# 05_MCU_PC.net
KiCad netlist of a schematic drawn in Altium Designer
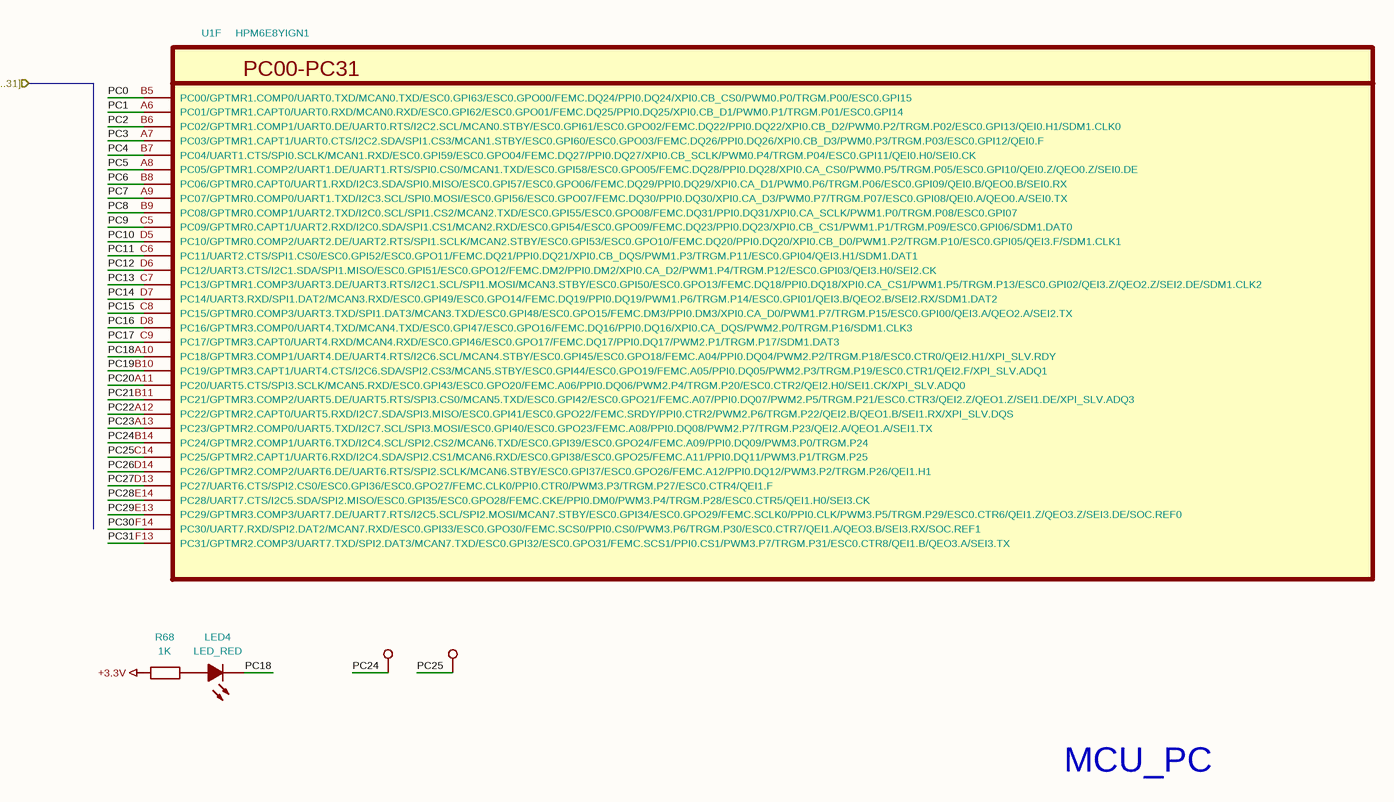
[diagram p0: 05.MCU_PC.SchDoc]

(export (version "E")
  (design (tool "Eeschema 10.0.6"))
  (components
    (comp (ref "LED4") (value "LED_RED") (libsource (lib "01-HPM-Peripheral") (part "LED_RED")))
    (comp (ref "R68") (value "1K") (libsource (lib "02_HPM_Resistor") (part "1K_0402")))
    (comp (ref "TP33") (value "0.5mm") (libsource (lib "01-HPM-Peripheral") (part "TestPoint-0.5mm")))
    (comp (ref "TP35") (value "0.5mm") (libsource (lib "01-HPM-Peripheral") (part "TestPoint-0.5mm")))
    (comp (ref "U1") (value "HPM6E8YIGN1") (libsource (lib "HPM6E00") (part "HPM6E8YIGN1")))
  )
  (nets
    (net (code "1") (name "+3.3V") (class "Default")
      (node (ref "R68") (pin "1") (pinfunction "1_1") (pintype "passive"))
    )
    (net (code "2") (name "/PC0") (class "Default")
      (node (ref "U1") (pin "B5") (pinfunction "PC00/GPTMR1.COMP0/UART0.TXD/MCAN0.TXD/ESC0.GPI63/ESC0.GPO00/FEMC.DQ24/PPI0.DQ24/XPI0.CB_CS0/PWM0.P0/TRGM.P00/ESC0.GPI15_B5") (pintype "passive"))
    )
    (net (code "3") (name "/PC1") (class "Default")
      (node (ref "U1") (pin "A6") (pinfunction "PC01/GPTMR1.CAPT0/UART0.RXD/MCAN0.RXD/ESC0.GPI62/ESC0.GPO01/FEMC.DQ25/PPI0.DQ25/XPI0.CB_D1/PWM0.P1/TRGM.P01/ESC0.GPI14_A6") (pintype "passive"))
    )
    (net (code "4") (name "/PC2") (class "Default")
      (node (ref "U1") (pin "B6") (pinfunction "PC02/GPTMR1.COMP1/UART0.DE/UART0.RTS/I2C2.SCL/MCAN0.STBY/ESC0.GPI61/ESC0.GPO02/FEMC.DQ22/PPI0.DQ22/XPI0.CB_D2/PWM0.P2/TRGM.P02/ESC0.GPI13/QEI0.H1/SDM1.CLK0_B6") (pintype "passive"))
    )
    (net (code "5") (name "/PC3") (class "Default")
      (node (ref "U1") (pin "A7") (pinfunction "PC03/GPTMR1.CAPT1/UART0.CTS/I2C2.SDA/SPI1.CS3/MCAN1.STBY/ESC0.GPI60/ESC0.GPO03/FEMC.DQ26/PPI0.DQ26/XPI0.CB_D3/PWM0.P3/TRGM.P03/ESC0.GPI12/QEI0.F_A7") (pintype "passive"))
    )
    (net (code "6") (name "/PC4") (class "Default")
      (node (ref "U1") (pin "B7") (pinfunction "PC04/UART1.CTS/SPI0.SCLK/MCAN1.RXD/ESC0.GPI59/ESC0.GPO04/FEMC.DQ27/PPI0.DQ27/XPI0.CB_SCLK/PWM0.P4/TRGM.P04/ESC0.GPI11/QEI0.H0/SEI0.CK_B7") (pintype "passive"))
    )
    (net (code "7") (name "/PC5") (class "Default")
      (node (ref "U1") (pin "A8") (pinfunction "PC05/GPTMR1.COMP2/UART1.DE/UART1.RTS/SPI0.CS0/MCAN1.TXD/ESC0.GPI58/ESC0.GPO05/FEMC.DQ28/PPI0.DQ28/XPI0.CA_CS0/PWM0.P5/TRGM.P05/ESC0.GPI10/QEI0.Z/QEO0.Z/SEI0.DE_A8") (pintype "passive"))
    )
    (net (code "8") (name "/PC6") (class "Default")
      (node (ref "U1") (pin "B8") (pinfunction "PC06/GPTMR0.CAPT0/UART1.RXD/I2C3.SDA/SPI0.MISO/ESC0.GPI57/ESC0.GPO06/FEMC.DQ29/PPI0.DQ29/XPI0.CA_D1/PWM0.P6/TRGM.P06/ESC0.GPI09/QEI0.B/QEO0.B/SEI0.RX_B8") (pintype "passive"))
    )
    (net (code "9") (name "/PC7") (class "Default")
      (node (ref "U1") (pin "A9") (pinfunction "PC07/GPTMR0.COMP0/UART1.TXD/I2C3.SCL/SPI0.MOSI/ESC0.GPI56/ESC0.GPO07/FEMC.DQ30/PPI0.DQ30/XPI0.CA_D3/PWM0.P7/TRGM.P07/ESC0.GPI08/QEI0.A/QEO0.A/SEI0.TX_A9") (pintype "passive"))
    )
    (net (code "10") (name "/PC8") (class "Default")
      (node (ref "U1") (pin "B9") (pinfunction "PC08/GPTMR0.COMP1/UART2.TXD/I2C0.SCL/SPI1.CS2/MCAN2.TXD/ESC0.GPI55/ESC0.GPO08/FEMC.DQ31/PPI0.DQ31/XPI0.CA_SCLK/PWM1.P0/TRGM.P08/ESC0.GPI07_B9") (pintype "passive"))
    )
    (net (code "11") (name "/PC9") (class "Default")
      (node (ref "U1") (pin "C5") (pinfunction "PC09/GPTMR0.CAPT1/UART2.RXD/I2C0.SDA/SPI1.CS1/MCAN2.RXD/ESC0.GPI54/ESC0.GPO09/FEMC.DQ23/PPI0.DQ23/XPI0.CB_CS1/PWM1.P1/TRGM.P09/ESC0.GPI06/SDM1.DAT0_C5") (pintype "passive"))
    )
    (net (code "12") (name "/PC10") (class "Default")
      (node (ref "U1") (pin "D5") (pinfunction "PC10/GPTMR0.COMP2/UART2.DE/UART2.RTS/SPI1.SCLK/MCAN2.STBY/ESC0.GPI53/ESC0.GPO10/FEMC.DQ20/PPI0.DQ20/XPI0.CB_D0/PWM1.P2/TRGM.P10/ESC0.GPI05/QEI3.F/SDM1.CLK1_D5") (pintype "passive"))
    )
    (net (code "13") (name "/PC11") (class "Default")
      (node (ref "U1") (pin "C6") (pinfunction "PC11/UART2.CTS/SPI1.CS0/ESC0.GPI52/ESC0.GPO11/FEMC.DQ21/PPI0.DQ21/XPI0.CB_DQS/PWM1.P3/TRGM.P11/ESC0.GPI04/QEI3.H1/SDM1.DAT1_C6") (pintype "passive"))
    )
    (net (code "14") (name "/PC12") (class "Default")
      (node (ref "U1") (pin "D6") (pinfunction "PC12/UART3.CTS/I2C1.SDA/SPI1.MISO/ESC0.GPI51/ESC0.GPO12/FEMC.DM2/PPI0.DM2/XPI0.CA_D2/PWM1.P4/TRGM.P12/ESC0.GPI03/QEI3.H0/SEI2.CK_D6") (pintype "passive"))
    )
    (net (code "15") (name "/PC13") (class "Default")
      (node (ref "U1") (pin "C7") (pinfunction "PC13/GPTMR1.COMP3/UART3.DE/UART3.RTS/I2C1.SCL/SPI1.MOSI/MCAN3.STBY/ESC0.GPI50/ESC0.GPO13/FEMC.DQ18/PPI0.DQ18/XPI0.CA_CS1/PWM1.P5/TRGM.P13/ESC0.GPI02/QEI3.Z/QEO2.Z/SEI2.DE/SDM1.CLK2_C7") (pintype "passive"))
    )
    (net (code "16") (name "/PC14") (class "Default")
      (node (ref "U1") (pin "D7") (pinfunction "PC14/UART3.RXD/SPI1.DAT2/MCAN3.RXD/ESC0.GPI49/ESC0.GPO14/FEMC.DQ19/PPI0.DQ19/PWM1.P6/TRGM.P14/ESC0.GPI01/QEI3.B/QEO2.B/SEI2.RX/SDM1.DAT2_D7") (pintype "passive"))
    )
    (net (code "17") (name "/PC15") (class "Default")
      (node (ref "U1") (pin "C8") (pinfunction "PC15/GPTMR0.COMP3/UART3.TXD/SPI1.DAT3/MCAN3.TXD/ESC0.GPI48/ESC0.GPO15/FEMC.DM3/PPI0.DM3/XPI0.CA_D0/PWM1.P7/TRGM.P15/ESC0.GPI00/QEI3.A/QEO2.A/SEI2.TX_C8") (pintype "passive"))
    )
    (net (code "18") (name "/PC16") (class "Default")
      (node (ref "U1") (pin "D8") (pinfunction "PC16/GPTMR3.COMP0/UART4.TXD/MCAN4.TXD/ESC0.GPI47/ESC0.GPO16/FEMC.DQ16/PPI0.DQ16/XPI0.CA_DQS/PWM2.P0/TRGM.P16/SDM1.CLK3_D8") (pintype "passive"))
    )
    (net (code "19") (name "/PC17") (class "Default")
      (node (ref "U1") (pin "C9") (pinfunction "PC17/GPTMR3.CAPT0/UART4.RXD/MCAN4.RXD/ESC0.GPI46/ESC0.GPO17/FEMC.DQ17/PPI0.DQ17/PWM2.P1/TRGM.P17/SDM1.DAT3_C9") (pintype "passive"))
    )
    (net (code "20") (name "/PC18") (class "Default")
      (node (ref "LED4") (pin "1") (pinfunction "K_1") (pintype "passive"))
      (node (ref "U1") (pin "A10") (pinfunction "PC18/GPTMR3.COMP1/UART4.DE/UART4.RTS/I2C6.SCL/MCAN4.STBY/ESC0.GPI45/ESC0.GPO18/FEMC.A04/PPI0.DQ04/PWM2.P2/TRGM.P18/ESC0.CTR0/QEI2.H1/XPI_SLV.RDY_A10") (pintype "passive"))
    )
    (net (code "21") (name "/PC19") (class "Default")
      (node (ref "U1") (pin "B10") (pinfunction "PC19/GPTMR3.CAPT1/UART4.CTS/I2C6.SDA/SPI2.CS3/MCAN5.STBY/ESC0.GPI44/ESC0.GPO19/FEMC.A05/PPI0.DQ05/PWM2.P3/TRGM.P19/ESC0.CTR1/QEI2.F/XPI_SLV.ADQ1_B10") (pintype "passive"))
    )
    (net (code "22") (name "/PC20") (class "Default")
      (node (ref "U1") (pin "A11") (pinfunction "PC20/UART5.CTS/SPI3.SCLK/MCAN5.RXD/ESC0.GPI43/ESC0.GPO20/FEMC.A06/PPI0.DQ06/PWM2.P4/TRGM.P20/ESC0.CTR2/QEI2.H0/SEI1.CK/XPI_SLV.ADQ0_A11") (pintype "passive"))
    )
    (net (code "23") (name "/PC21") (class "Default")
      (node (ref "U1") (pin "B11") (pinfunction "PC21/GPTMR3.COMP2/UART5.DE/UART5.RTS/SPI3.CS0/MCAN5.TXD/ESC0.GPI42/ESC0.GPO21/FEMC.A07/PPI0.DQ07/PWM2.P5/TRGM.P21/ESC0.CTR3/QEI2.Z/QEO1.Z/SEI1.DE/XPI_SLV.ADQ3_B11") (pintype "passive"))
    )
    (net (code "24") (name "/PC22") (class "Default")
      (node (ref "U1") (pin "A12") (pinfunction "PC22/GPTMR2.CAPT0/UART5.RXD/I2C7.SDA/SPI3.MISO/ESC0.GPI41/ESC0.GPO22/FEMC.SRDY/PPI0.CTR2/PWM2.P6/TRGM.P22/QEI2.B/QEO1.B/SEI1.RX/XPI_SLV.DQS_A12") (pintype "passive"))
    )
    (net (code "25") (name "/PC23") (class "Default")
      (node (ref "U1") (pin "A13") (pinfunction "PC23/GPTMR2.COMP0/UART5.TXD/I2C7.SCL/SPI3.MOSI/ESC0.GPI40/ESC0.GPO23/FEMC.A08/PPI0.DQ08/PWM2.P7/TRGM.P23/QEI2.A/QEO1.A/SEI1.TX_A13") (pintype "passive"))
    )
    (net (code "26") (name "/PC24") (class "Default")
      (node (ref "TP33") (pin "1") (pinfunction "1_1") (pintype "passive"))
      (node (ref "U1") (pin "B14") (pinfunction "PC24/GPTMR2.COMP1/UART6.TXD/I2C4.SCL/SPI2.CS2/MCAN6.TXD/ESC0.GPI39/ESC0.GPO24/FEMC.A09/PPI0.DQ09/PWM3.P0/TRGM.P24_B14") (pintype "passive"))
    )
    (net (code "27") (name "/PC25") (class "Default")
      (node (ref "TP35") (pin "1") (pinfunction "1_1") (pintype "passive"))
      (node (ref "U1") (pin "C14") (pinfunction "PC25/GPTMR2.CAPT1/UART6.RXD/I2C4.SDA/SPI2.CS1/MCAN6.RXD/ESC0.GPI38/ESC0.GPO25/FEMC.A11/PPI0.DQ11/PWM3.P1/TRGM.P25_C14") (pintype "passive"))
    )
    (net (code "28") (name "/PC26") (class "Default")
      (node (ref "U1") (pin "D14") (pinfunction "PC26/GPTMR2.COMP2/UART6.DE/UART6.RTS/SPI2.SCLK/MCAN6.STBY/ESC0.GPI37/ESC0.GPO26/FEMC.A12/PPI0.DQ12/PWM3.P2/TRGM.P26/QEI1.H1_D14") (pintype "passive"))
    )
    (net (code "29") (name "/PC27") (class "Default")
      (node (ref "U1") (pin "D13") (pinfunction "PC27/UART6.CTS/SPI2.CS0/ESC0.GPI36/ESC0.GPO27/FEMC.CLK0/PPI0.CTR0/PWM3.P3/TRGM.P27/ESC0.CTR4/QEI1.F_D13") (pintype "passive"))
    )
    (net (code "30") (name "/PC28") (class "Default")
      (node (ref "U1") (pin "E14") (pinfunction "PC28/UART7.CTS/I2C5.SDA/SPI2.MISO/ESC0.GPI35/ESC0.GPO28/FEMC.CKE/PPI0.DM0/PWM3.P4/TRGM.P28/ESC0.CTR5/QEI1.H0/SEI3.CK_E14") (pintype "passive"))
    )
    (net (code "31") (name "/PC29") (class "Default")
      (node (ref "U1") (pin "E13") (pinfunction "PC29/GPTMR3.COMP3/UART7.DE/UART7.RTS/I2C5.SCL/SPI2.MOSI/MCAN7.STBY/ESC0.GPI34/ESC0.GPO29/FEMC.SCLK0/PPI0.CLK/PWM3.P5/TRGM.P29/ESC0.CTR6/QEI1.Z/QEO3.Z/SEI3.DE/SOC.REF0_E13") (pintype "passive"))
    )
    (net (code "32") (name "/PC30") (class "Default")
      (node (ref "U1") (pin "F14") (pinfunction "PC30/UART7.RXD/SPI2.DAT2/MCAN7.RXD/ESC0.GPI33/ESC0.GPO30/FEMC.SCS0/PPI0.CS0/PWM3.P6/TRGM.P30/ESC0.CTR7/QEI1.A/QEO3.B/SEI3.RX/SOC.REF1_F14") (pintype "passive"))
    )
    (net (code "33") (name "/PC31") (class "Default")
      (node (ref "U1") (pin "F13") (pinfunction "PC31/GPTMR2.COMP3/UART7.TXD/SPI2.DAT3/MCAN7.TXD/ESC0.GPI32/ESC0.GPO31/FEMC.SCS1/PPI0.CS1/PWM3.P7/TRGM.P31/ESC0.CTR8/QEI1.B/QEO3.A/SEI3.TX_F13") (pintype "passive"))
    )
    (net (code "35") (name "Net-(LED4-A)") (class "Default")
      (node (ref "LED4") (pin "2") (pinfunction "A_2") (pintype "passive"))
      (node (ref "R68") (pin "2") (pinfunction "2_2") (pintype "passive"))
    )
  )
)
